# 3_Airframe-Memory_1.net
KiCad netlist of a schematic drawn in Altium Designer
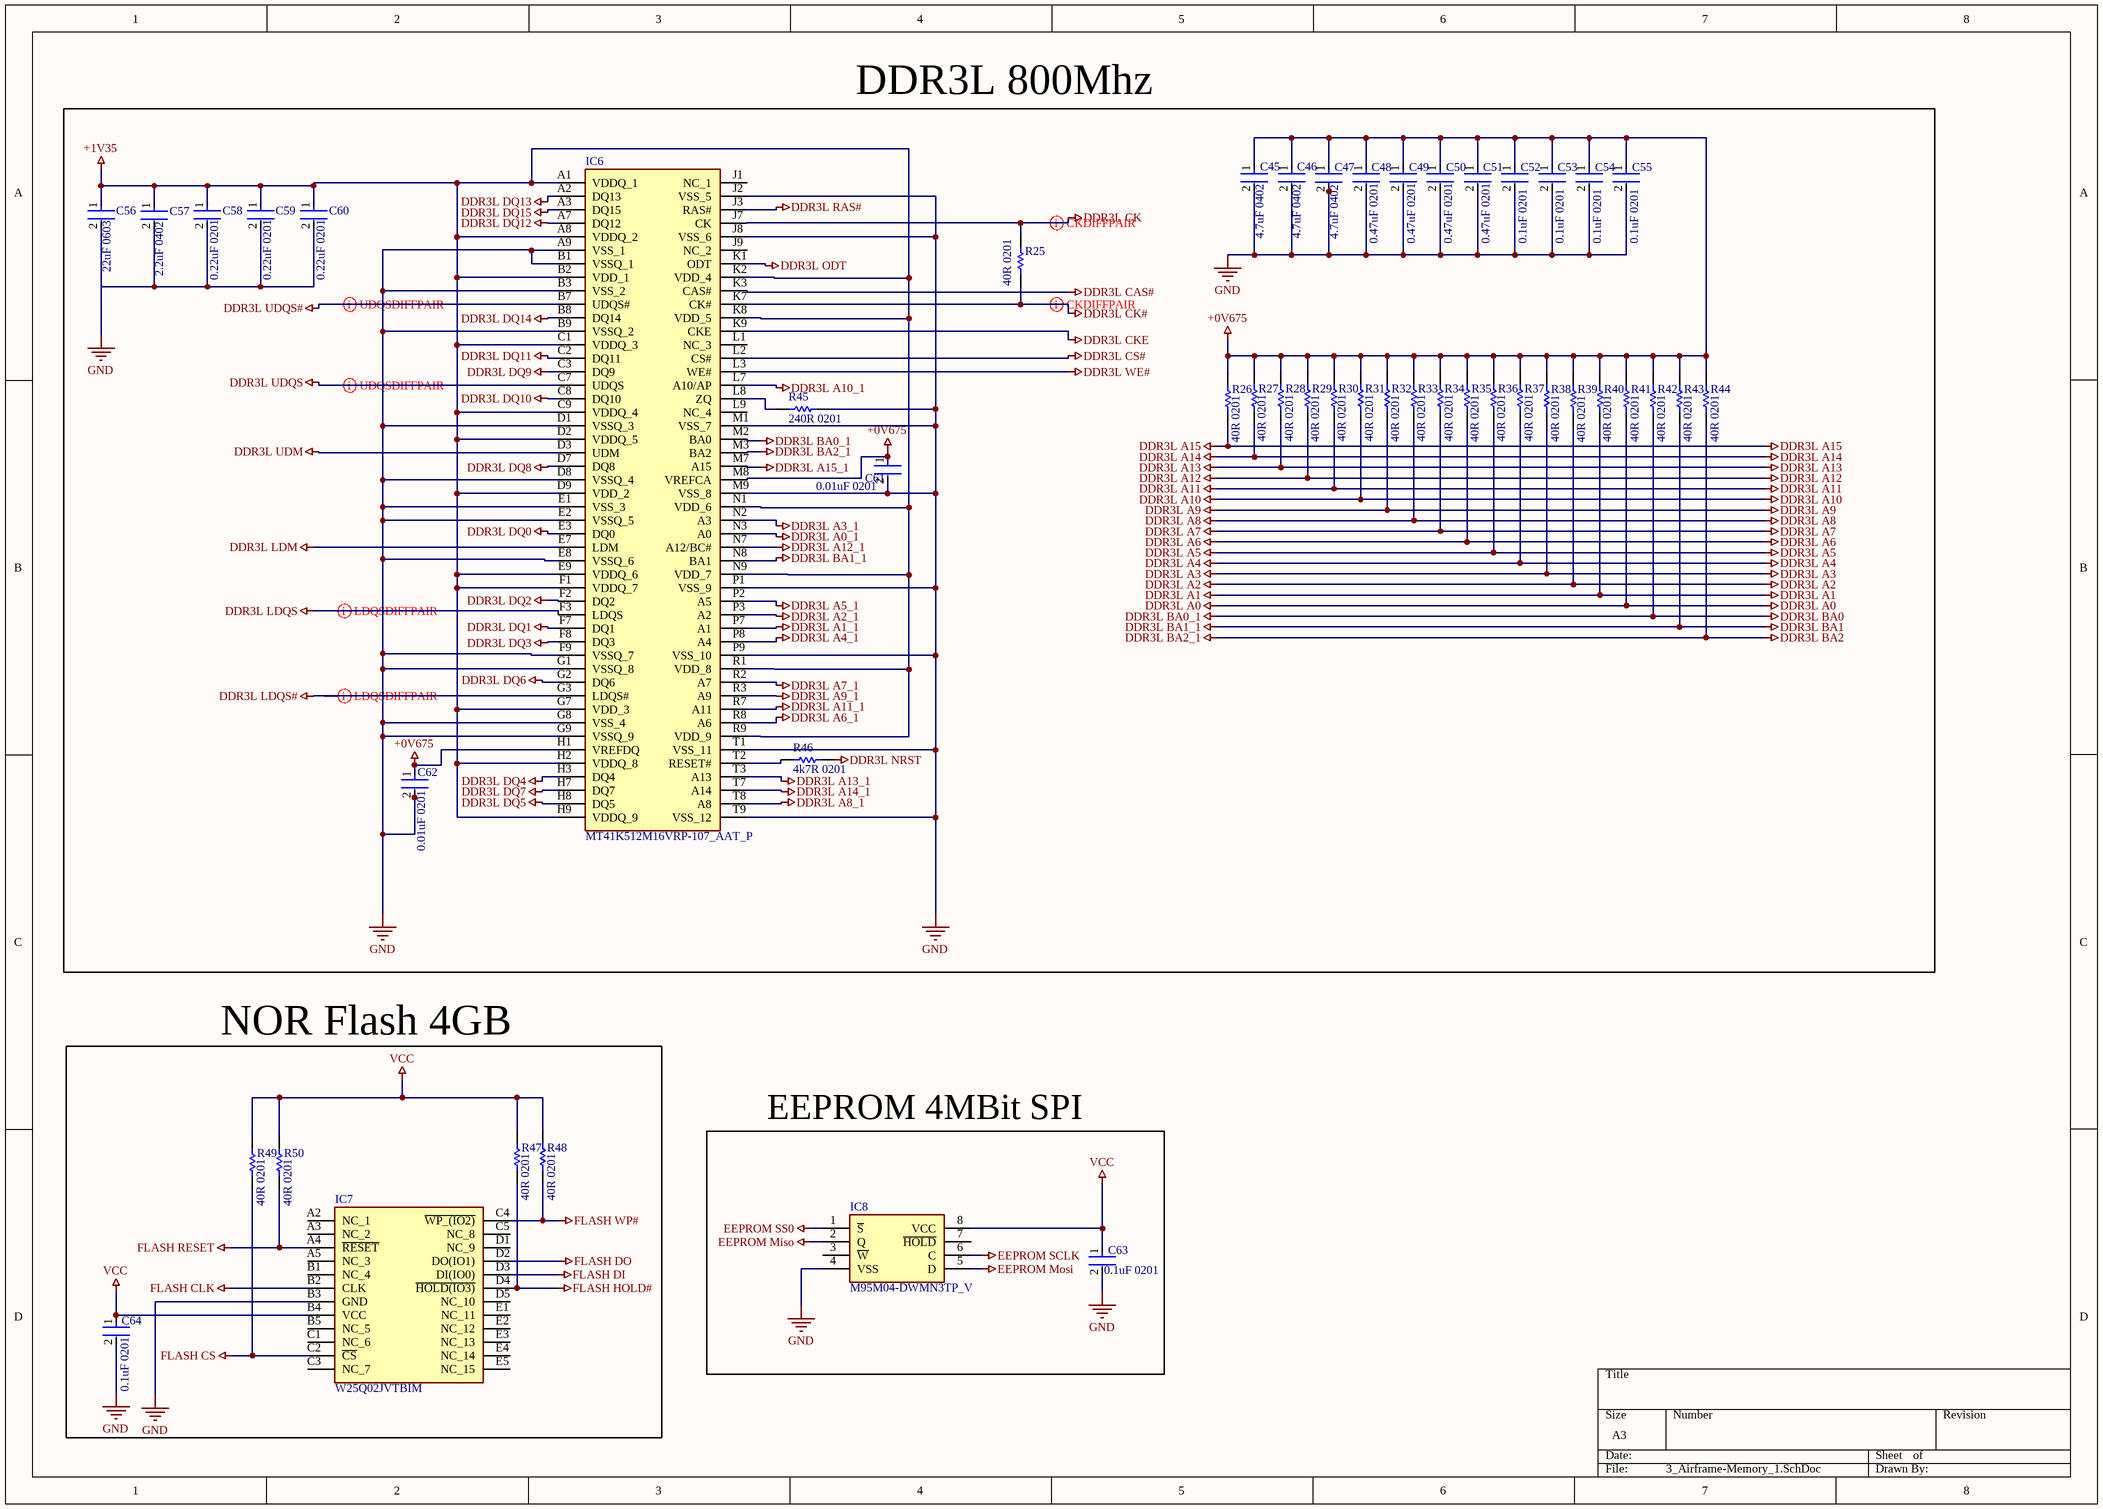
[diagram p0: 3_Airframe-Memory_1.SchDoc]

(export (version "E")
  (design (tool "Eeschema 10.0.6"))
  (components
    (comp (ref "C45")
      (value "4.7uF 0402")
      (footprint "FP-C0402C225M9PACTU-MFG")
      (description "CAP CER 2.2UF 6.3V X5R 0402")
      (fields (field (name "VOLTAGE") "6.3V") (field (name "TOLERANCE") "20%"))
      (libsource (lib "Altium Content Vault") (part "b4654b650e69147ec39a6b967a45e02"))
    )
    (comp (ref "C46")
      (value "4.7uF 0402")
      (footprint "FP-C0402C225M9PACTU-MFG")
      (description "CAP CER 2.2UF 6.3V X5R 0402")
      (fields (field (name "VOLTAGE") "6.3V") (field (name "TOLERANCE") "20%"))
      (libsource (lib "Altium Content Vault") (part "b4654b650e69147ec39a6b967a45e02"))
    )
    (comp (ref "C47")
      (value "4.7uF 0402")
      (footprint "FP-C0402C225M9PACTU-MFG")
      (description "CAP CER 2.2UF 6.3V X5R 0402")
      (fields (field (name "VOLTAGE") "6.3V") (field (name "TOLERANCE") "20%"))
      (libsource (lib "Altium Content Vault") (part "b4654b650e69147ec39a6b967a45e02"))
    )
    (comp (ref "C48")
      (value "0.47uF 0201")
      (footprint "FP-C0603-030-0_03-IPC_C")
      (description "Multilayer Ceramic Capacitors 220nF ±10% 6.3V X6S SMD 0201")
      (fields (field (name "TOLERANCE") "10%"))
      (libsource (lib "Altium Content Vault") (part "02cd4be3c70576c341d710602a673aa"))
    )
    (comp (ref "C49")
      (value "0.47uF 0201")
      (footprint "FP-C0603-030-0_03-IPC_C")
      (description "Multilayer Ceramic Capacitors 220nF ±10% 6.3V X6S SMD 0201")
      (fields (field (name "TOLERANCE") "10%"))
      (libsource (lib "Altium Content Vault") (part "02cd4be3c70576c341d710602a673aa"))
    )
    (comp (ref "C50")
      (value "0.47uF 0201")
      (footprint "FP-C0603-030-0_03-IPC_C")
      (description "Multilayer Ceramic Capacitors 220nF ±10% 6.3V X6S SMD 0201")
      (fields (field (name "TOLERANCE") "10%"))
      (libsource (lib "Altium Content Vault") (part "02cd4be3c70576c341d710602a673aa"))
    )
    (comp (ref "C51")
      (value "0.47uF 0201")
      (footprint "FP-C0603-030-0_03-IPC_C")
      (description "Multilayer Ceramic Capacitors 220nF ±10% 6.3V X6S SMD 0201")
      (fields (field (name "TOLERANCE") "10%"))
      (libsource (lib "Altium Content Vault") (part "02cd4be3c70576c341d710602a673aa"))
    )
    (comp (ref "C52")
      (value "0.1uF 0201")
      (footprint "FP-C0603-030-0_03-IPC_C")
      (description "Multilayer Ceramic Capacitors 220nF ±10% 6.3V X6S SMD 0201")
      (fields (field (name "TOLERANCE") "10%"))
      (libsource (lib "Altium Content Vault") (part "02cd4be3c70576c341d710602a673aa"))
    )
    (comp (ref "C53")
      (value "0.1uF 0201")
      (footprint "FP-C0603-030-0_03-IPC_C")
      (description "Multilayer Ceramic Capacitors 220nF ±10% 6.3V X6S SMD 0201")
      (fields (field (name "TOLERANCE") "10%"))
      (libsource (lib "Altium Content Vault") (part "02cd4be3c70576c341d710602a673aa"))
    )
    (comp (ref "C54")
      (value "0.1uF 0201")
      (footprint "FP-C0603-030-0_03-IPC_C")
      (description "Multilayer Ceramic Capacitors 220nF ±10% 6.3V X6S SMD 0201")
      (fields (field (name "TOLERANCE") "10%"))
      (libsource (lib "Altium Content Vault") (part "02cd4be3c70576c341d710602a673aa"))
    )
    (comp (ref "C55")
      (value "0.1uF 0201")
      (footprint "FP-C0603-030-0_03-IPC_C")
      (description "Multilayer Ceramic Capacitors 220nF ±10% 6.3V X6S SMD 0201")
      (fields (field (name "TOLERANCE") "10%"))
      (libsource (lib "Altium Content Vault") (part "02cd4be3c70576c341d710602a673aa"))
    )
    (comp (ref "C56")
      (value "22uF 0603")
      (footprint "FP-GRM188-0_2-IPC_C")
      (description "Chip Multilayer Ceramic Capacitors for General Purpose, 0603, 22uF, X5R, 15%, 20%, 10V")
      (fields (field (name "TOLERANCE") "20%"))
      (libsource (lib "Altium Content Vault") (part "11868f565c42a9108669ba33697ecf6"))
    )
    (comp (ref "C57")
      (value "2.2uF 0402")
      (footprint "FP-C0402C225M9PACTU-MFG")
      (description "CAP CER 2.2UF 6.3V X5R 0402")
      (fields (field (name "VOLTAGE") "6.3V") (field (name "TOLERANCE") "20%"))
      (libsource (lib "Altium Content Vault") (part "b4654b650e69147ec39a6b967a45e02"))
    )
    (comp (ref "C58")
      (value "0.22uF 0201")
      (footprint "FP-C0603-030-0_03-IPC_C")
      (description "Multilayer Ceramic Capacitors 220nF ±10% 6.3V X6S SMD 0201")
      (fields (field (name "TOLERANCE") "10%"))
      (libsource (lib "Altium Content Vault") (part "02cd4be3c70576c341d710602a673aa"))
    )
    (comp (ref "C59")
      (value "0.22uF 0201")
      (footprint "FP-C0603-030-0_03-IPC_C")
      (description "Multilayer Ceramic Capacitors 220nF ±10% 6.3V X6S SMD 0201")
      (fields (field (name "TOLERANCE") "10%"))
      (libsource (lib "Altium Content Vault") (part "02cd4be3c70576c341d710602a673aa"))
    )
    (comp (ref "C60")
      (value "0.22uF 0201")
      (footprint "FP-C0603-030-0_03-IPC_C")
      (description "Multilayer Ceramic Capacitors 220nF ±10% 6.3V X6S SMD 0201")
      (fields (field (name "TOLERANCE") "10%"))
      (libsource (lib "Altium Content Vault") (part "02cd4be3c70576c341d710602a673aa"))
    )
    (comp (ref "C61")
      (value "0.01uF 0201")
      (footprint "FP-C0603-030-0_03-IPC_C")
      (description "Multilayer Ceramic Capacitors 220nF ±10% 6.3V X6S SMD 0201")
      (fields (field (name "TOLERANCE") "10%"))
      (libsource (lib "Altium Content Vault") (part "02cd4be3c70576c341d710602a673aa"))
    )
    (comp (ref "C62")
      (value "0.01uF 0201")
      (footprint "FP-C0603-030-0_03-IPC_C")
      (description "Multilayer Ceramic Capacitors 220nF ±10% 6.3V X6S SMD 0201")
      (fields (field (name "TOLERANCE") "10%"))
      (libsource (lib "Altium Content Vault") (part "02cd4be3c70576c341d710602a673aa"))
    )
    (comp (ref "C63")
      (value "0.1uF 0201")
      (footprint "FP-C0603-030-0_03-IPC_C")
      (description "Multilayer Ceramic Capacitors 220nF ±10% 6.3V X6S SMD 0201")
      (fields (field (name "TOLERANCE") "10%"))
      (libsource (lib "Altium Content Vault") (part "02cd4be3c70576c341d710602a673aa"))
    )
    (comp (ref "C64")
      (value "0.1uF 0201")
      (footprint "FP-C0603-030-0_03-IPC_C")
      (description "Multilayer Ceramic Capacitors 220nF ±10% 6.3V X6S SMD 0201")
      (fields (field (name "TOLERANCE") "10%"))
      (libsource (lib "Altium Content Vault") (part "02cd4be3c70576c341d710602a673aa"))
    )
    (comp (ref "IC6")
      (value "MT41K512M16VRP-107_AAT_P")
      (footprint "SamacSys:BGA96C80P9X16_800X1400X120")
      (description "Integrated Circuit")
      (fields
        (field (name "MANUFACTURER_PART_NUMBER") "MT41K512M16VRP-107 AAT:P")
        (field (name "MOUSER PART NUMBER") "340-446578-TRAY")
      )
      (libsource (lib "*") (part "MT41K512M16VRP-107_AAT_P"))
    )
    (comp (ref "IC7")
      (value "W25Q02JVTBIM")
      (footprint "SamacSys:BGA24C100P5X5_600X800X120")
      (description "Integrated Circuit")
      (fields (field (name "MOUSER PART NUMBER") "454-W25Q02JVTBIM"))
      (libsource (lib "*") (part "W25Q02JVTBIM"))
    )
    (comp (ref "IC8")
      (value "M95M04-DWMN3TP_V")
      (footprint "SamacSys:SOIC127P600X175-8N")
      (description "Integrated Circuit")
      (fields
        (field (name "MANUFACTURER_PART_NUMBER") "M95M04-DWMN3TP/V")
        (field (name "MOUSER PART NUMBER") "511-M95M04-DWMN3TP/V")
      )
      (libsource (lib "*") (part "M95M04-DWMN3TP_V"))
    )
    (comp (ref "R25")
      (value "40R 0201")
      (footprint "RESC0603X28X15NL05T05")
      (fields (field (name "MANUFACTURER") "Vishay") (field (name "PART NUMBER") "CRCW0201100RFNED"))
      (libsource (lib "Altium Content Vault") (part "RES"))
    )
    (comp (ref "R26")
      (value "40R 0201")
      (footprint "RESC0603X28X15NL05T05")
      (fields (field (name "MANUFACTURER") "Vishay") (field (name "PART NUMBER") "CRCW0201100RFNED"))
      (libsource (lib "Altium Content Vault") (part "RES"))
    )
    (comp (ref "R27")
      (value "40R 0201")
      (footprint "RESC0603X28X15NL05T05")
      (fields (field (name "MANUFACTURER") "Vishay") (field (name "PART NUMBER") "CRCW0201100RFNED"))
      (libsource (lib "Altium Content Vault") (part "RES"))
    )
    (comp (ref "R28")
      (value "40R 0201")
      (footprint "RESC0603X28X15NL05T05")
      (fields (field (name "MANUFACTURER") "Vishay") (field (name "PART NUMBER") "CRCW0201100RFNED"))
      (libsource (lib "Altium Content Vault") (part "RES"))
    )
    (comp (ref "R29")
      (value "40R 0201")
      (footprint "RESC0603X28X15NL05T05")
      (fields (field (name "MANUFACTURER") "Vishay") (field (name "PART NUMBER") "CRCW0201100RFNED"))
      (libsource (lib "Altium Content Vault") (part "RES"))
    )
    (comp (ref "R30")
      (value "40R 0201")
      (footprint "RESC0603X28X15NL05T05")
      (fields (field (name "MANUFACTURER") "Vishay") (field (name "PART NUMBER") "CRCW0201100RFNED"))
      (libsource (lib "Altium Content Vault") (part "RES"))
    )
    (comp (ref "R31")
      (value "40R 0201")
      (footprint "RESC0603X28X15NL05T05")
      (fields (field (name "MANUFACTURER") "Vishay") (field (name "PART NUMBER") "CRCW0201100RFNED"))
      (libsource (lib "Altium Content Vault") (part "RES"))
    )
    (comp (ref "R32")
      (value "40R 0201")
      (footprint "RESC0603X28X15NL05T05")
      (fields (field (name "MANUFACTURER") "Vishay") (field (name "PART NUMBER") "CRCW0201100RFNED"))
      (libsource (lib "Altium Content Vault") (part "RES"))
    )
    (comp (ref "R33")
      (value "40R 0201")
      (footprint "RESC0603X28X15NL05T05")
      (fields (field (name "MANUFACTURER") "Vishay") (field (name "PART NUMBER") "CRCW0201100RFNED"))
      (libsource (lib "Altium Content Vault") (part "RES"))
    )
    (comp (ref "R34")
      (value "40R 0201")
      (footprint "RESC0603X28X15NL05T05")
      (fields (field (name "MANUFACTURER") "Vishay") (field (name "PART NUMBER") "CRCW0201100RFNED"))
      (libsource (lib "Altium Content Vault") (part "RES"))
    )
    (comp (ref "R35")
      (value "40R 0201")
      (footprint "RESC0603X28X15NL05T05")
      (fields (field (name "MANUFACTURER") "Vishay") (field (name "PART NUMBER") "CRCW0201100RFNED"))
      (libsource (lib "Altium Content Vault") (part "RES"))
    )
    (comp (ref "R36")
      (value "40R 0201")
      (footprint "RESC0603X28X15NL05T05")
      (fields (field (name "MANUFACTURER") "Vishay") (field (name "PART NUMBER") "CRCW0201100RFNED"))
      (libsource (lib "Altium Content Vault") (part "RES"))
    )
    (comp (ref "R37")
      (value "40R 0201")
      (footprint "RESC0603X28X15NL05T05")
      (fields (field (name "MANUFACTURER") "Vishay") (field (name "PART NUMBER") "CRCW0201100RFNED"))
      (libsource (lib "Altium Content Vault") (part "RES"))
    )
    (comp (ref "R38")
      (value "40R 0201")
      (footprint "RESC0603X28X15NL05T05")
      (fields (field (name "MANUFACTURER") "Vishay") (field (name "PART NUMBER") "CRCW0201100RFNED"))
      (libsource (lib "Altium Content Vault") (part "RES"))
    )
    (comp (ref "R39")
      (value "40R 0201")
      (footprint "RESC0603X28X15NL05T05")
      (fields (field (name "MANUFACTURER") "Vishay") (field (name "PART NUMBER") "CRCW0201100RFNED"))
      (libsource (lib "Altium Content Vault") (part "RES"))
    )
    (comp (ref "R40")
      (value "40R 0201")
      (footprint "RESC0603X28X15NL05T05")
      (fields (field (name "MANUFACTURER") "Vishay") (field (name "PART NUMBER") "CRCW0201100RFNED"))
      (libsource (lib "Altium Content Vault") (part "RES"))
    )
    (comp (ref "R41")
      (value "40R 0201")
      (footprint "RESC0603X28X15NL05T05")
      (fields (field (name "MANUFACTURER") "Vishay") (field (name "PART NUMBER") "CRCW0201100RFNED"))
      (libsource (lib "Altium Content Vault") (part "RES"))
    )
    (comp (ref "R42")
      (value "40R 0201")
      (footprint "RESC0603X28X15NL05T05")
      (fields (field (name "MANUFACTURER") "Vishay") (field (name "PART NUMBER") "CRCW0201100RFNED"))
      (libsource (lib "Altium Content Vault") (part "RES"))
    )
    (comp (ref "R43")
      (value "40R 0201")
      (footprint "RESC0603X28X15NL05T05")
      (fields (field (name "MANUFACTURER") "Vishay") (field (name "PART NUMBER") "CRCW0201100RFNED"))
      (libsource (lib "Altium Content Vault") (part "RES"))
    )
    (comp (ref "R44")
      (value "40R 0201")
      (footprint "RESC0603X28X15NL05T05")
      (fields (field (name "MANUFACTURER") "Vishay") (field (name "PART NUMBER") "CRCW0201100RFNED"))
      (libsource (lib "Altium Content Vault") (part "RES"))
    )
    (comp (ref "R45")
      (value "240R 0201")
      (footprint "RESC0603X28X15NL05T05")
      (fields (field (name "MANUFACTURER") "Vishay") (field (name "PART NUMBER") "CRCW0201100RFNED"))
      (libsource (lib "Altium Content Vault") (part "RES"))
    )
    (comp (ref "R46")
      (value "4k7R 0201")
      (footprint "RESC0603X28X15NL05T05")
      (fields (field (name "MANUFACTURER") "Vishay") (field (name "PART NUMBER") "CRCW0201100RFNED"))
      (libsource (lib "Altium Content Vault") (part "RES"))
    )
    (comp (ref "R47")
      (value "40R 0201")
      (footprint "RESC0603X28X15NL05T05")
      (fields (field (name "MANUFACTURER") "Vishay") (field (name "PART NUMBER") "CRCW0201100RFNED"))
      (libsource (lib "Altium Content Vault") (part "RES"))
    )
    (comp (ref "R48")
      (value "40R 0201")
      (footprint "RESC0603X28X15NL05T05")
      (fields (field (name "MANUFACTURER") "Vishay") (field (name "PART NUMBER") "CRCW0201100RFNED"))
      (libsource (lib "Altium Content Vault") (part "RES"))
    )
    (comp (ref "R49")
      (value "40R 0201")
      (footprint "RESC0603X28X15NL05T05")
      (fields (field (name "MANUFACTURER") "Vishay") (field (name "PART NUMBER") "CRCW0201100RFNED"))
      (libsource (lib "Altium Content Vault") (part "RES"))
    )
    (comp (ref "R50")
      (value "40R 0201")
      (footprint "RESC0603X28X15NL05T05")
      (fields (field (name "MANUFACTURER") "Vishay") (field (name "PART NUMBER") "CRCW0201100RFNED"))
      (libsource (lib "Altium Content Vault") (part "RES"))
    )
  )
  (nets
    (net (code "1") (name "+0V675") (class "Default")
      (node (ref "C45") (pin "1") (pinfunction "1_1") (pintype "passive"))
      (node (ref "C46") (pin "1") (pinfunction "1_1") (pintype "passive"))
      (node (ref "C47") (pin "1") (pinfunction "1_1") (pintype "passive"))
      (node (ref "C48") (pin "1") (pinfunction "1_1") (pintype "passive"))
      (node (ref "C49") (pin "1") (pinfunction "1_1") (pintype "passive"))
      (node (ref "C50") (pin "1") (pinfunction "1_1") (pintype "passive"))
      (node (ref "C51") (pin "1") (pinfunction "1_1") (pintype "passive"))
      (node (ref "C52") (pin "1") (pinfunction "1_1") (pintype "passive"))
      (node (ref "C53") (pin "1") (pinfunction "1_1") (pintype "passive"))
      (node (ref "C54") (pin "1") (pinfunction "1_1") (pintype "passive"))
      (node (ref "C55") (pin "1") (pinfunction "1_1") (pintype "passive"))
      (node (ref "C61") (pin "1") (pinfunction "1_1") (pintype "passive"))
      (node (ref "C62") (pin "1") (pinfunction "1_1") (pintype "passive"))
      (node (ref "IC6") (pin "H1") (pinfunction "VREFDQ_H1") (pintype "passive"))
      (node (ref "IC6") (pin "M8") (pinfunction "VREFCA_M8") (pintype "passive"))
      (node (ref "R26") (pin "2") (pinfunction "2_2") (pintype "passive"))
      (node (ref "R27") (pin "2") (pinfunction "2_2") (pintype "passive"))
      (node (ref "R28") (pin "2") (pinfunction "2_2") (pintype "passive"))
      (node (ref "R29") (pin "2") (pinfunction "2_2") (pintype "passive"))
      (node (ref "R30") (pin "2") (pinfunction "2_2") (pintype "passive"))
      (node (ref "R31") (pin "2") (pinfunction "2_2") (pintype "passive"))
      (node (ref "R32") (pin "2") (pinfunction "2_2") (pintype "passive"))
      (node (ref "R33") (pin "2") (pinfunction "2_2") (pintype "passive"))
      (node (ref "R34") (pin "2") (pinfunction "2_2") (pintype "passive"))
      (node (ref "R35") (pin "2") (pinfunction "2_2") (pintype "passive"))
      (node (ref "R36") (pin "2") (pinfunction "2_2") (pintype "passive"))
      (node (ref "R37") (pin "2") (pinfunction "2_2") (pintype "passive"))
      (node (ref "R38") (pin "2") (pinfunction "2_2") (pintype "passive"))
      (node (ref "R39") (pin "2") (pinfunction "2_2") (pintype "passive"))
      (node (ref "R40") (pin "2") (pinfunction "2_2") (pintype "passive"))
      (node (ref "R41") (pin "2") (pinfunction "2_2") (pintype "passive"))
      (node (ref "R42") (pin "2") (pinfunction "2_2") (pintype "passive"))
      (node (ref "R43") (pin "2") (pinfunction "2_2") (pintype "passive"))
      (node (ref "R44") (pin "2") (pinfunction "2_2") (pintype "passive"))
    )
    (net (code "2") (name "+1V35") (class "Default")
      (node (ref "C56") (pin "1") (pinfunction "1_1") (pintype "passive"))
      (node (ref "C57") (pin "1") (pinfunction "1_1") (pintype "passive"))
      (node (ref "C58") (pin "1") (pinfunction "1_1") (pintype "passive"))
      (node (ref "C59") (pin "1") (pinfunction "1_1") (pintype "passive"))
      (node (ref "C60") (pin "1") (pinfunction "1_1") (pintype "passive"))
      (node (ref "IC6") (pin "A1") (pinfunction "VDDQ_1_A1") (pintype "passive"))
      (node (ref "IC6") (pin "A8") (pinfunction "VDDQ_2_A8") (pintype "passive"))
      (node (ref "IC6") (pin "B2") (pinfunction "VDD_1_B2") (pintype "passive"))
      (node (ref "IC6") (pin "C1") (pinfunction "VDDQ_3_C1") (pintype "passive"))
      (node (ref "IC6") (pin "C9") (pinfunction "VDDQ_4_C9") (pintype "passive"))
      (node (ref "IC6") (pin "D2") (pinfunction "VDDQ_5_D2") (pintype "passive"))
      (node (ref "IC6") (pin "D9") (pinfunction "VDD_2_D9") (pintype "passive"))
      (node (ref "IC6") (pin "E9") (pinfunction "VDDQ_6_E9") (pintype "passive"))
      (node (ref "IC6") (pin "F1") (pinfunction "VDDQ_7_F1") (pintype "passive"))
      (node (ref "IC6") (pin "G7") (pinfunction "VDD_3_G7") (pintype "passive"))
      (node (ref "IC6") (pin "H2") (pinfunction "VDDQ_8_H2") (pintype "passive"))
      (node (ref "IC6") (pin "H9") (pinfunction "VDDQ_9_H9") (pintype "passive"))
      (node (ref "IC6") (pin "K2") (pinfunction "VDD_4_K2") (pintype "passive"))
      (node (ref "IC6") (pin "K8") (pinfunction "VDD_5_K8") (pintype "passive"))
      (node (ref "IC6") (pin "N1") (pinfunction "VDD_6_N1") (pintype "passive"))
      (node (ref "IC6") (pin "N9") (pinfunction "VDD_7_N9") (pintype "passive"))
      (node (ref "IC6") (pin "R1") (pinfunction "VDD_8_R1") (pintype "passive"))
      (node (ref "IC6") (pin "R9") (pinfunction "VDD_9_R9") (pintype "passive"))
    )
    (net (code "3") (name "DDR3L A0") (class "Default")
      (node (ref "R41") (pin "1") (pinfunction "1_1") (pintype "passive"))
    )
    (net (code "4") (name "DDR3L A0_1") (class "Default")
      (node (ref "IC6") (pin "N3") (pinfunction "A0_N3") (pintype "passive"))
    )
    (net (code "5") (name "DDR3L A1") (class "Default")
      (node (ref "R40") (pin "1") (pinfunction "1_1") (pintype "passive"))
    )
    (net (code "6") (name "DDR3L A1_1") (class "Default")
      (node (ref "IC6") (pin "P7") (pinfunction "A1_P7") (pintype "passive"))
    )
    (net (code "7") (name "DDR3L A2") (class "Default")
      (node (ref "R39") (pin "1") (pinfunction "1_1") (pintype "passive"))
    )
    (net (code "8") (name "DDR3L A2_1") (class "Default")
      (node (ref "IC6") (pin "P3") (pinfunction "A2_P3") (pintype "passive"))
    )
    (net (code "9") (name "DDR3L A3") (class "Default")
      (node (ref "R38") (pin "1") (pinfunction "1_1") (pintype "passive"))
    )
    (net (code "10") (name "DDR3L A3_1") (class "Default")
      (node (ref "IC6") (pin "N2") (pinfunction "A3_N2") (pintype "passive"))
    )
    (net (code "11") (name "DDR3L A4") (class "Default")
      (node (ref "R37") (pin "1") (pinfunction "1_1") (pintype "passive"))
    )
    (net (code "12") (name "DDR3L A4_1") (class "Default")
      (node (ref "IC6") (pin "P8") (pinfunction "A4_P8") (pintype "passive"))
    )
    (net (code "13") (name "DDR3L A5") (class "Default")
      (node (ref "R36") (pin "1") (pinfunction "1_1") (pintype "passive"))
    )
    (net (code "14") (name "DDR3L A5_1") (class "Default")
      (node (ref "IC6") (pin "P2") (pinfunction "A5_P2") (pintype "passive"))
    )
    (net (code "15") (name "DDR3L A6") (class "Default")
      (node (ref "R35") (pin "1") (pinfunction "1_1") (pintype "passive"))
    )
    (net (code "16") (name "DDR3L A6_1") (class "Default")
      (node (ref "IC6") (pin "R8") (pinfunction "A6_R8") (pintype "passive"))
    )
    (net (code "17") (name "DDR3L A7") (class "Default")
      (node (ref "R34") (pin "1") (pinfunction "1_1") (pintype "passive"))
    )
    (net (code "18") (name "DDR3L A7_1") (class "Default")
      (node (ref "IC6") (pin "R2") (pinfunction "A7_R2") (pintype "passive"))
    )
    (net (code "19") (name "DDR3L A8") (class "Default")
      (node (ref "R33") (pin "1") (pinfunction "1_1") (pintype "passive"))
    )
    (net (code "20") (name "DDR3L A8_1") (class "Default")
      (node (ref "IC6") (pin "T8") (pinfunction "A8_T8") (pintype "passive"))
    )
    (net (code "21") (name "DDR3L A9") (class "Default")
      (node (ref "R32") (pin "1") (pinfunction "1_1") (pintype "passive"))
    )
    (net (code "22") (name "DDR3L A9_1") (class "Default")
      (node (ref "IC6") (pin "R3") (pinfunction "A9_R3") (pintype "passive"))
    )
    (net (code "23") (name "DDR3L A10") (class "Default")
      (node (ref "R31") (pin "1") (pinfunction "1_1") (pintype "passive"))
    )
    (net (code "24") (name "DDR3L A10_1") (class "Default")
      (node (ref "IC6") (pin "L7") (pinfunction "A10/AP_L7") (pintype "passive"))
    )
    (net (code "25") (name "DDR3L A11") (class "Default")
      (node (ref "R30") (pin "1") (pinfunction "1_1") (pintype "passive"))
    )
    (net (code "26") (name "DDR3L A11_1") (class "Default")
      (node (ref "IC6") (pin "R7") (pinfunction "A11_R7") (pintype "passive"))
    )
    (net (code "27") (name "DDR3L A12") (class "Default")
      (node (ref "R29") (pin "1") (pinfunction "1_1") (pintype "passive"))
    )
    (net (code "28") (name "DDR3L A12_1") (class "Default")
      (node (ref "IC6") (pin "N7") (pinfunction "A12/BC#_N7") (pintype "passive"))
    )
    (net (code "29") (name "DDR3L A13") (class "Default")
      (node (ref "R28") (pin "1") (pinfunction "1_1") (pintype "passive"))
    )
    (net (code "30") (name "DDR3L A13_1") (class "Default")
      (node (ref "IC6") (pin "T3") (pinfunction "A13_T3") (pintype "passive"))
    )
    (net (code "31") (name "DDR3L A14") (class "Default")
      (node (ref "R27") (pin "1") (pinfunction "1_1") (pintype "passive"))
    )
    (net (code "32") (name "DDR3L A14_1") (class "Default")
      (node (ref "IC6") (pin "T7") (pinfunction "A14_T7") (pintype "passive"))
    )
    (net (code "33") (name "DDR3L A15") (class "Default")
      (node (ref "R26") (pin "1") (pinfunction "1_1") (pintype "passive"))
    )
    (net (code "34") (name "DDR3L A15_1") (class "Default")
      (node (ref "IC6") (pin "M7") (pinfunction "A15_M7") (pintype "passive"))
    )
    (net (code "35") (name "DDR3L BA0") (class "Default")
      (node (ref "IC6") (pin "M2") (pinfunction "BA0_M2") (pintype "passive"))
      (node (ref "R42") (pin "1") (pinfunction "1_1") (pintype "passive"))
    )
    (net (code "36") (name "DDR3L BA1") (class "Default")
      (node (ref "IC6") (pin "N8") (pinfunction "BA1_N8") (pintype "passive"))
      (node (ref "R43") (pin "1") (pinfunction "1_1") (pintype "passive"))
    )
    (net (code "37") (name "DDR3L BA2") (class "Default")
      (node (ref "IC6") (pin "M3") (pinfunction "BA2_M3") (pintype "passive"))
      (node (ref "R44") (pin "1") (pinfunction "1_1") (pintype "passive"))
    )
    (net (code "38") (name "DDR3L CAS#") (class "Default")
      (node (ref "IC6") (pin "K3") (pinfunction "CAS#_K3") (pintype "passive"))
    )
    (net (code "39") (name "DDR3L CK") (class "Default")
      (node (ref "IC6") (pin "J7") (pinfunction "CK_J7") (pintype "passive"))
      (node (ref "R25") (pin "2") (pinfunction "2_2") (pintype "passive"))
    )
    (net (code "40") (name "DDR3L CK#") (class "Default")
      (node (ref "IC6") (pin "K7") (pinfunction "CK#_K7") (pintype "passive"))
      (node (ref "R25") (pin "1") (pinfunction "1_1") (pintype "passive"))
    )
    (net (code "41") (name "DDR3L CKE") (class "Default")
      (node (ref "IC6") (pin "K9") (pinfunction "CKE_K9") (pintype "passive"))
    )
    (net (code "42") (name "DDR3L CS#") (class "Default")
      (node (ref "IC6") (pin "L2") (pinfunction "CS#_L2") (pintype "passive"))
    )
    (net (code "43") (name "DDR3L DQ0") (class "Default")
      (node (ref "IC6") (pin "E3") (pinfunction "DQ0_E3") (pintype "passive"))
    )
    (net (code "44") (name "DDR3L DQ1") (class "Default")
      (node (ref "IC6") (pin "F7") (pinfunction "DQ1_F7") (pintype "passive"))
    )
    (net (code "45") (name "DDR3L DQ2") (class "Default")
      (node (ref "IC6") (pin "F2") (pinfunction "DQ2_F2") (pintype "passive"))
    )
    (net (code "46") (name "DDR3L DQ3") (class "Default")
      (node (ref "IC6") (pin "F8") (pinfunction "DQ3_F8") (pintype "passive"))
    )
    (net (code "47") (name "DDR3L DQ4") (class "Default")
      (node (ref "IC6") (pin "H3") (pinfunction "DQ4_H3") (pintype "passive"))
    )
    (net (code "48") (name "DDR3L DQ5") (class "Default")
      (node (ref "IC6") (pin "H8") (pinfunction "DQ5_H8") (pintype "passive"))
    )
    (net (code "49") (name "DDR3L DQ6") (class "Default")
      (node (ref "IC6") (pin "G2") (pinfunction "DQ6_G2") (pintype "passive"))
    )
    (net (code "50") (name "DDR3L DQ7") (class "Default")
      (node (ref "IC6") (pin "H7") (pinfunction "DQ7_H7") (pintype "passive"))
    )
    (net (code "51") (name "DDR3L DQ8") (class "Default")
      (node (ref "IC6") (pin "D7") (pinfunction "DQ8_D7") (pintype "passive"))
    )
    (net (code "52") (name "DDR3L DQ9") (class "Default")
      (node (ref "IC6") (pin "C3") (pinfunction "DQ9_C3") (pintype "passive"))
    )
    (net (code "53") (name "DDR3L DQ10") (class "Default")
      (node (ref "IC6") (pin "C8") (pinfunction "DQ10_C8") (pintype "passive"))
    )
    (net (code "54") (name "DDR3L DQ11") (class "Default")
      (node (ref "IC6") (pin "C2") (pinfunction "DQ11_C2") (pintype "passive"))
    )
    (net (code "55") (name "DDR3L DQ12") (class "Default")
      (node (ref "IC6") (pin "A7") (pinfunction "DQ12_A7") (pintype "passive"))
    )
    (net (code "56") (name "DDR3L DQ13") (class "Default")
      (node (ref "IC6") (pin "A2") (pinfunction "DQ13_A2") (pintype "passive"))
    )
    (net (code "57") (name "DDR3L DQ14") (class "Default")
      (node (ref "IC6") (pin "B8") (pinfunction "DQ14_B8") (pintype "passive"))
    )
    (net (code "58") (name "DDR3L DQ15") (class "Default")
      (node (ref "IC6") (pin "A3") (pinfunction "DQ15_A3") (pintype "passive"))
    )
    (net (code "59") (name "DDR3L LDM") (class "Default")
      (node (ref "IC6") (pin "E7") (pinfunction "LDM_E7") (pintype "passive"))
    )
    (net (code "60") (name "DDR3L LDQS") (class "Default")
      (node (ref "IC6") (pin "F3") (pinfunction "LDQS_F3") (pintype "passive"))
    )
    (net (code "61") (name "DDR3L LDQS#") (class "Default")
      (node (ref "IC6") (pin "G3") (pinfunction "LDQS#_G3") (pintype "passive"))
    )
    (net (code "62") (name "DDR3L NRST") (class "Default")
      (node (ref "R46") (pin "2") (pinfunction "2_2") (pintype "passive"))
    )
    (net (code "63") (name "DDR3L ODT") (class "Default")
      (node (ref "IC6") (pin "K1") (pinfunction "ODT_K1") (pintype "passive"))
    )
    (net (code "64") (name "DDR3L RAS#") (class "Default")
      (node (ref "IC6") (pin "J3") (pinfunction "RAS#_J3") (pintype "passive"))
    )
    (net (code "65") (name "DDR3L UDM") (class "Default")
      (node (ref "IC6") (pin "D3") (pinfunction "UDM_D3") (pintype "passive"))
    )
    (net (code "66") (name "DDR3L UDQS") (class "Default")
      (node (ref "IC6") (pin "C7") (pinfunction "UDQS_C7") (pintype "passive"))
    )
    (net (code "67") (name "DDR3L UDQS#") (class "Default")
      (node (ref "IC6") (pin "B7") (pinfunction "UDQS#_B7") (pintype "passive"))
    )
    (net (code "68") (name "DDR3L WE#") (class "Default")
      (node (ref "IC6") (pin "L3") (pinfunction "WE#_L3") (pintype "passive"))
    )
    (net (code "69") (name "EEPROM Miso") (class "Default")
      (node (ref "IC8") (pin "2") (pinfunction "Q_2") (pintype "passive"))
    )
    (net (code "70") (name "EEPROM Mosi") (class "Default")
      (node (ref "IC8") (pin "5") (pinfunction "D_5") (pintype "passive"))
    )
    (net (code "71") (name "EEPROM SCLK") (class "Default")
      (node (ref "IC8") (pin "6") (pinfunction "C_6") (pintype "passive"))
    )
    (net (code "72") (name "EEPROM SS0") (class "Default")
      (node (ref "IC8") (pin "1") (pinfunction "~{S}_1") (pintype "passive"))
    )
    (net (code "73") (name "FLASH CLK") (class "Default")
      (node (ref "IC7") (pin "B2") (pinfunction "CLK_B2") (pintype "passive"))
    )
    (net (code "74") (name "FLASH CS") (class "Default")
      (node (ref "IC7") (pin "C2") (pinfunction "~{CS}_C2") (pintype "passive"))
      (node (ref "R49") (pin "1") (pinfunction "1_1") (pintype "passive"))
    )
    (net (code "75") (name "FLASH DI") (class "Default")
      (node (ref "IC7") (pin "D3") (pinfunction "DI(IO0)_D3") (pintype "passive"))
    )
    (net (code "76") (name "FLASH DO") (class "Default")
      (node (ref "IC7") (pin "D2") (pinfunction "DO(IO1)_D2") (pintype "passive"))
    )
    (net (code "77") (name "FLASH HOLD#") (class "Default")
      (node (ref "IC7") (pin "D4") (pinfunction "~{HOLD(IO3)}_D4") (pintype "passive"))
      (node (ref "R47") (pin "1") (pinfunction "1_1") (pintype "passive"))
    )
    (net (code "78") (name "FLASH RESET") (class "Default")
      (node (ref "IC7") (pin "A4") (pinfunction "~{RESET}_A4") (pintype "passive"))
      (node (ref "R50") (pin "1") (pinfunction "1_1") (pintype "passive"))
    )
    (net (code "79") (name "FLASH WP#") (class "Default")
      (node (ref "IC7") (pin "C4") (pinfunction "~{WP_(IO2)}_C4") (pintype "passive"))
      (node (ref "R48") (pin "1") (pinfunction "1_1") (pintype "passive"))
    )
    (net (code "80") (name "GND") (class "Default")
      (node (ref "C45") (pin "2") (pinfunction "2_2") (pintype "passive"))
      (node (ref "C46") (pin "2") (pinfunction "2_2") (pintype "passive"))
      (node (ref "C47") (pin "2") (pinfunction "2_2") (pintype "passive"))
      (node (ref "C48") (pin "2") (pinfunction "2_2") (pintype "passive"))
      (node (ref "C49") (pin "2") (pinfunction "2_2") (pintype "passive"))
      (node (ref "C50") (pin "2") (pinfunction "2_2") (pintype "passive"))
      (node (ref "C51") (pin "2") (pinfunction "2_2") (pintype "passive"))
      (node (ref "C52") (pin "2") (pinfunction "2_2") (pintype "passive"))
      (node (ref "C53") (pin "2") (pinfunction "2_2") (pintype "passive"))
      (node (ref "C54") (pin "2") (pinfunction "2_2") (pintype "passive"))
      (node (ref "C55") (pin "2") (pinfunction "2_2") (pintype "passive"))
      (node (ref "C56") (pin "2") (pinfunction "2_2") (pintype "passive"))
      (node (ref "C57") (pin "2") (pinfunction "2_2") (pintype "passive"))
      (node (ref "C58") (pin "2") (pinfunction "2_2") (pintype "passive"))
      (node (ref "C59") (pin "2") (pinfunction "2_2") (pintype "passive"))
      (node (ref "C60") (pin "2") (pinfunction "2_2") (pintype "passive"))
      (node (ref "C61") (pin "2") (pinfunction "2_2") (pintype "passive"))
      (node (ref "C62") (pin "2") (pinfunction "2_2") (pintype "passive"))
      (node (ref "C63") (pin "2") (pinfunction "2_2") (pintype "passive"))
      (node (ref "C64") (pin "2") (pinfunction "2_2") (pintype "passive"))
      (node (ref "IC6") (pin "A9") (pinfunction "VSS_1_A9") (pintype "passive"))
      (node (ref "IC6") (pin "B1") (pinfunction "VSSQ_1_B1") (pintype "passive"))
      (node (ref "IC6") (pin "B3") (pinfunction "VSS_2_B3") (pintype "passive"))
      (node (ref "IC6") (pin "B9") (pinfunction "VSSQ_2_B9") (pintype "passive"))
      (node (ref "IC6") (pin "D1") (pinfunction "VSSQ_3_D1") (pintype "passive"))
      (node (ref "IC6") (pin "D8") (pinfunction "VSSQ_4_D8") (pintype "passive"))
      (node (ref "IC6") (pin "E1") (pinfunction "VSS_3_E1") (pintype "passive"))
      (node (ref "IC6") (pin "E2") (pinfunction "VSSQ_5_E2") (pintype "passive"))
      (node (ref "IC6") (pin "E8") (pinfunction "VSSQ_6_E8") (pintype "passive"))
      (node (ref "IC6") (pin "F9") (pinfunction "VSSQ_7_F9") (pintype "passive"))
      (node (ref "IC6") (pin "G1") (pinfunction "VSSQ_8_G1") (pintype "passive"))
      (node (ref "IC6") (pin "G8") (pinfunction "VSS_4_G8") (pintype "passive"))
      (node (ref "IC6") (pin "G9") (pinfunction "VSSQ_9_G9") (pintype "passive"))
      (node (ref "IC6") (pin "J2") (pinfunction "VSS_5_J2") (pintype "passive"))
      (node (ref "IC6") (pin "J8") (pinfunction "VSS_6_J8") (pintype "passive"))
      (node (ref "IC6") (pin "M1") (pinfunction "VSS_7_M1") (pintype "passive"))
      (node (ref "IC6") (pin "M9") (pinfunction "VSS_8_M9") (pintype "passive"))
      (node (ref "IC6") (pin "P1") (pinfunction "VSS_9_P1") (pintype "passive"))
      (node (ref "IC6") (pin "P9") (pinfunction "VSS_10_P9") (pintype "passive"))
      (node (ref "IC6") (pin "T1") (pinfunction "VSS_11_T1") (pintype "passive"))
      (node (ref "IC6") (pin "T9") (pinfunction "VSS_12_T9") (pintype "passive"))
      (node (ref "IC7") (pin "B3") (pinfunction "GND_B3") (pintype "passive"))
      (node (ref "IC8") (pin "4") (pinfunction "VSS_4") (pintype "passive"))
      (node (ref "R45") (pin "2") (pinfunction "2_2") (pintype "passive"))
    )
    (net (code "81") (name "Net-(IC6-RESET#)") (class "Default")
      (node (ref "IC6") (pin "T2") (pinfunction "RESET#_T2") (pintype "passive"))
      (node (ref "R46") (pin "1") (pinfunction "1_1") (pintype "passive"))
    )
    (net (code "82") (name "Net-(IC6-ZQ)") (class "Default")
      (node (ref "IC6") (pin "L8") (pinfunction "ZQ_L8") (pintype "passive"))
      (node (ref "R45") (pin "1") (pinfunction "1_1") (pintype "passive"))
    )
    (net (code "83") (name "VCC") (class "Default")
      (node (ref "C63") (pin "1") (pinfunction "1_1") (pintype "passive"))
      (node (ref "C64") (pin "1") (pinfunction "1_1") (pintype "passive"))
      (node (ref "IC7") (pin "B4") (pinfunction "VCC_B4") (pintype "passive"))
      (node (ref "IC8") (pin "8") (pinfunction "VCC_8") (pintype "passive"))
      (node (ref "R47") (pin "2") (pinfunction "2_2") (pintype "passive"))
      (node (ref "R48") (pin "2") (pinfunction "2_2") (pintype "passive"))
      (node (ref "R49") (pin "2") (pinfunction "2_2") (pintype "passive"))
      (node (ref "R50") (pin "2") (pinfunction "2_2") (pintype "passive"))
    )
    (net (code "84") (name "unconnected-(IC6-NC_1-PadJ1)") (class "Default")
      (node (ref "IC6") (pin "J1") (pinfunction "NC_1_J1") (pintype "passive"))
    )
    (net (code "85") (name "unconnected-(IC6-NC_2-PadJ9)") (class "Default")
      (node (ref "IC6") (pin "J9") (pinfunction "NC_2_J9") (pintype "passive"))
    )
    (net (code "86") (name "unconnected-(IC6-NC_3-PadL1)") (class "Default")
      (node (ref "IC6") (pin "L1") (pinfunction "NC_3_L1") (pintype "passive"))
    )
    (net (code "87") (name "unconnected-(IC6-NC_4-PadL9)") (class "Default")
      (node (ref "IC6") (pin "L9") (pinfunction "NC_4_L9") (pintype "passive"))
    )
    (net (code "88") (name "unconnected-(IC7-NC_1-PadA2)") (class "Default")
      (node (ref "IC7") (pin "A2") (pinfunction "NC_1_A2") (pintype "passive"))
    )
    (net (code "89") (name "unconnected-(IC7-NC_2-PadA3)") (class "Default")
      (node (ref "IC7") (pin "A3") (pinfunction "NC_2_A3") (pintype "passive"))
    )
    (net (code "90") (name "unconnected-(IC7-NC_3-PadA5)") (class "Default")
      (node (ref "IC7") (pin "A5") (pinfunction "NC_3_A5") (pintype "passive"))
    )
    (net (code "91") (name "unconnected-(IC7-NC_4-PadB1)") (class "Default")
      (node (ref "IC7") (pin "B1") (pinfunction "NC_4_B1") (pintype "passive"))
    )
    (net (code "92") (name "unconnected-(IC7-NC_5-PadB5)") (class "Default")
      (node (ref "IC7") (pin "B5") (pinfunction "NC_5_B5") (pintype "passive"))
    )
    (net (code "93") (name "unconnected-(IC7-NC_6-PadC1)") (class "Default")
      (node (ref "IC7") (pin "C1") (pinfunction "NC_6_C1") (pintype "passive"))
    )
    (net (code "94") (name "unconnected-(IC7-NC_7-PadC3)") (class "Default")
      (node (ref "IC7") (pin "C3") (pinfunction "NC_7_C3") (pintype "passive"))
    )
    (net (code "95") (name "unconnected-(IC7-NC_8-PadC5)") (class "Default")
      (node (ref "IC7") (pin "C5") (pinfunction "NC_8_C5") (pintype "passive"))
    )
    (net (code "96") (name "unconnected-(IC7-NC_9-PadD1)") (class "Default")
      (node (ref "IC7") (pin "D1") (pinfunction "NC_9_D1") (pintype "passive"))
    )
    (net (code "97") (name "unconnected-(IC7-NC_10-PadD5)") (class "Default")
      (node (ref "IC7") (pin "D5") (pinfunction "NC_10_D5") (pintype "passive"))
    )
    (net (code "98") (name "unconnected-(IC7-NC_11-PadE1)") (class "Default")
      (node (ref "IC7") (pin "E1") (pinfunction "NC_11_E1") (pintype "passive"))
    )
    (net (code "99") (name "unconnected-(IC7-NC_12-PadE2)") (class "Default")
      (node (ref "IC7") (pin "E2") (pinfunction "NC_12_E2") (pintype "passive"))
    )
    (net (code "100") (name "unconnected-(IC7-NC_13-PadE3)") (class "Default")
      (node (ref "IC7") (pin "E3") (pinfunction "NC_13_E3") (pintype "passive"))
    )
    (net (code "101") (name "unconnected-(IC7-NC_14-PadE4)") (class "Default")
      (node (ref "IC7") (pin "E4") (pinfunction "NC_14_E4") (pintype "passive"))
    )
    (net (code "102") (name "unconnected-(IC7-NC_15-PadE5)") (class "Default")
      (node (ref "IC7") (pin "E5") (pinfunction "NC_15_E5") (pintype "passive"))
    )
    (net (code "103") (name "unconnected-(IC8-~{HOLD}-Pad7)") (class "Default")
      (node (ref "IC8") (pin "7") (pinfunction "~{HOLD}_7") (pintype "passive"))
    )
    (net (code "104") (name "unconnected-(IC8-~{W}-Pad3)") (class "Default")
      (node (ref "IC8") (pin "3") (pinfunction "~{W}_3") (pintype "passive"))
    )
  )
)
